# Rpi_GPIO.net
KiCad netlist of a schematic drawn in Altium Designer
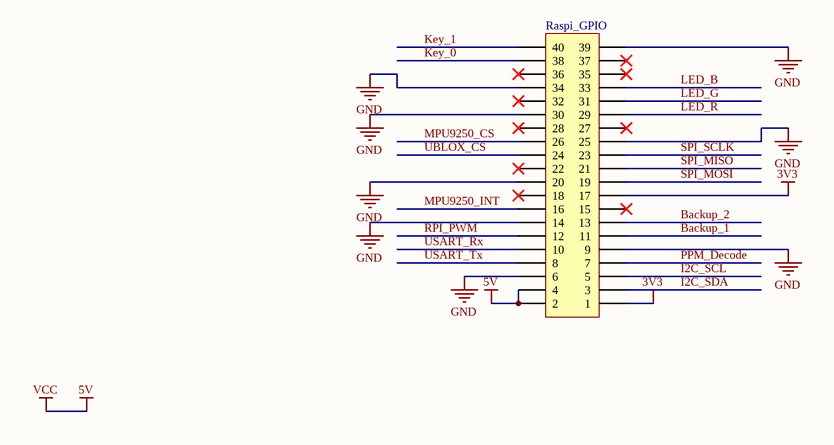
[diagram p0: Rpi_GPIO.SchDoc]

(export (version "E")
  (design (tool "Eeschema 10.0.6"))
  (components
    (comp (ref "Raspi_GPIO")
      (value "Header 20X2")
      (footprint "HDR2X20")
      (description "Header, 20-Pin, Dual row")
      (fields (field (name "PUBLISHER") "Altium Limited"))
      (libsource (lib "Miscellaneous Connectors") (part "Header 20X2"))
    )
  )
  (nets
    (net (code "1") (name "/Backup_1") (class "Default")
      (node (ref "Raspi_GPIO") (pin "11") (pinfunction "11_11") (pintype "passive"))
    )
    (net (code "2") (name "/Backup_2") (class "Default")
      (node (ref "Raspi_GPIO") (pin "13") (pinfunction "13_13") (pintype "passive"))
    )
    (net (code "3") (name "/I2C_SCL") (class "Default")
      (node (ref "Raspi_GPIO") (pin "5") (pinfunction "5_5") (pintype "passive"))
    )
    (net (code "4") (name "/I2C_SDA") (class "Default")
      (node (ref "Raspi_GPIO") (pin "3") (pinfunction "3_3") (pintype "passive"))
    )
    (net (code "5") (name "/Key_0") (class "Default")
      (node (ref "Raspi_GPIO") (pin "38") (pinfunction "38_38") (pintype "passive"))
    )
    (net (code "6") (name "/Key_1") (class "Default")
      (node (ref "Raspi_GPIO") (pin "40") (pinfunction "40_40") (pintype "passive"))
    )
    (net (code "7") (name "/LED_B") (class "Default")
      (node (ref "Raspi_GPIO") (pin "33") (pinfunction "33_33") (pintype "passive"))
    )
    (net (code "8") (name "/LED_G") (class "Default")
      (node (ref "Raspi_GPIO") (pin "31") (pinfunction "31_31") (pintype "passive"))
    )
    (net (code "9") (name "/LED_R") (class "Default")
      (node (ref "Raspi_GPIO") (pin "29") (pinfunction "29_29") (pintype "passive"))
    )
    (net (code "10") (name "/MPU9250_CS") (class "Default")
      (node (ref "Raspi_GPIO") (pin "26") (pinfunction "26_26") (pintype "passive"))
    )
    (net (code "11") (name "/MPU9250_INT") (class "Default")
      (node (ref "Raspi_GPIO") (pin "16") (pinfunction "16_16") (pintype "passive"))
    )
    (net (code "12") (name "/PPM_Decode") (class "Default")
      (node (ref "Raspi_GPIO") (pin "7") (pinfunction "7_7") (pintype "passive"))
    )
    (net (code "13") (name "/RPI_PWM") (class "Default")
      (node (ref "Raspi_GPIO") (pin "12") (pinfunction "12_12") (pintype "passive"))
    )
    (net (code "14") (name "/SPI_MISO") (class "Default")
      (node (ref "Raspi_GPIO") (pin "21") (pinfunction "21_21") (pintype "passive"))
    )
    (net (code "15") (name "/SPI_MOSI") (class "Default")
      (node (ref "Raspi_GPIO") (pin "19") (pinfunction "19_19") (pintype "passive"))
    )
    (net (code "16") (name "/SPI_SCLK") (class "Default")
      (node (ref "Raspi_GPIO") (pin "23") (pinfunction "23_23") (pintype "passive"))
    )
    (net (code "17") (name "/UBLOX_CS") (class "Default")
      (node (ref "Raspi_GPIO") (pin "24") (pinfunction "24_24") (pintype "passive"))
    )
    (net (code "18") (name "/USART_Rx") (class "Default")
      (node (ref "Raspi_GPIO") (pin "10") (pinfunction "10_10") (pintype "passive"))
    )
    (net (code "19") (name "/USART_Tx") (class "Default")
      (node (ref "Raspi_GPIO") (pin "8") (pinfunction "8_8") (pintype "passive"))
    )
    (net (code "20") (name "3V3") (class "Default")
      (node (ref "Raspi_GPIO") (pin "1") (pinfunction "1_1") (pintype "passive"))
      (node (ref "Raspi_GPIO") (pin "17") (pinfunction "17_17") (pintype "passive"))
    )
    (net (code "21") (name "5V") (class "Default")
      (node (ref "Raspi_GPIO") (pin "2") (pinfunction "2_2") (pintype "passive"))
      (node (ref "Raspi_GPIO") (pin "4") (pinfunction "4_4") (pintype "passive"))
    )
    (net (code "22") (name "GND") (class "Default")
      (node (ref "Raspi_GPIO") (pin "14") (pinfunction "14_14") (pintype "passive"))
      (node (ref "Raspi_GPIO") (pin "20") (pinfunction "20_20") (pintype "passive"))
      (node (ref "Raspi_GPIO") (pin "25") (pinfunction "25_25") (pintype "passive"))
      (node (ref "Raspi_GPIO") (pin "30") (pinfunction "30_30") (pintype "passive"))
      (node (ref "Raspi_GPIO") (pin "34") (pinfunction "34_34") (pintype "passive"))
      (node (ref "Raspi_GPIO") (pin "39") (pinfunction "39_39") (pintype "passive"))
      (node (ref "Raspi_GPIO") (pin "6") (pinfunction "6_6") (pintype "passive"))
      (node (ref "Raspi_GPIO") (pin "9") (pinfunction "9_9") (pintype "passive"))
    )
    (net (code "23") (name "unconnected-(Raspi_GPIO-Pad15)") (class "Default")
      (node (ref "Raspi_GPIO") (pin "15") (pinfunction "15_15") (pintype "passive+no_connect"))
    )
    (net (code "24") (name "unconnected-(Raspi_GPIO-Pad18)") (class "Default")
      (node (ref "Raspi_GPIO") (pin "18") (pinfunction "18_18") (pintype "passive+no_connect"))
    )
    (net (code "25") (name "unconnected-(Raspi_GPIO-Pad22)") (class "Default")
      (node (ref "Raspi_GPIO") (pin "22") (pinfunction "22_22") (pintype "passive+no_connect"))
    )
    (net (code "26") (name "unconnected-(Raspi_GPIO-Pad27)") (class "Default")
      (node (ref "Raspi_GPIO") (pin "27") (pinfunction "27_27") (pintype "passive+no_connect"))
    )
    (net (code "27") (name "unconnected-(Raspi_GPIO-Pad28)") (class "Default")
      (node (ref "Raspi_GPIO") (pin "28") (pinfunction "28_28") (pintype "passive+no_connect"))
    )
    (net (code "28") (name "unconnected-(Raspi_GPIO-Pad32)") (class "Default")
      (node (ref "Raspi_GPIO") (pin "32") (pinfunction "32_32") (pintype "passive+no_connect"))
    )
    (net (code "29") (name "unconnected-(Raspi_GPIO-Pad35)") (class "Default")
      (node (ref "Raspi_GPIO") (pin "35") (pinfunction "35_35") (pintype "passive+no_connect"))
    )
    (net (code "30") (name "unconnected-(Raspi_GPIO-Pad36)") (class "Default")
      (node (ref "Raspi_GPIO") (pin "36") (pinfunction "36_36") (pintype "passive+no_connect"))
    )
    (net (code "31") (name "unconnected-(Raspi_GPIO-Pad37)") (class "Default")
      (node (ref "Raspi_GPIO") (pin "37") (pinfunction "37_37") (pintype "passive+no_connect"))
    )
  )
)
